# throughhole.net
KiCad netlist of a schematic drawn in EAGLE
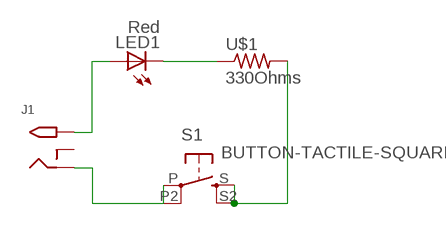
[diagram p0: schematic, sheet 1]

(export (version "E")
  (design (tool "Eeschema 10.0.6"))
  (components
    (comp (ref "J1")
      (value "2.1MMJACKTHM")
      (footprint "eagle-import:PJ-102A")
      (libsource (lib "eagle-import") (part "2.1MMJACKTHM"))
    )
    (comp (ref "LED1")
      (value "Red")
      (footprint "eagle-import:LED5MM")
      (libsource (lib "eagle-import") (part "LED5MM"))
    )
    (comp (ref "S1")
      (value "BUTTON-TACTILE-SQUARE")
      (footprint "eagle-import:BUTTON-TACTILE-SQUARE-ADAFRUIT1010")
      (libsource (lib "eagle-import") (part "BUTTON-TACTILE-SQUARE"))
    )
    (comp (ref "U$1")
      (value "330Ohms")
      (footprint "eagle-import:RESAD1160W55L680D260_HS")
      (libsource (lib "eagle-import") (part "RESISTORTH-1/4W-CARBON"))
    )
  )
  (nets
    (net (code "1") (name "Net-(J1-PadTIP)") (class "Default")
      (node (ref "J1") (pin "TIP") (pinfunction "TIP_TIP") (pintype "bidirectional"))
      (node (ref "LED1") (pin "A") (pinfunction "A_A") (pintype "passive"))
    )
    (net (code "2") (name "Net-(LED1-C)") (class "Default")
      (node (ref "LED1") (pin "K") (pinfunction "C_K") (pintype "passive"))
      (node (ref "U$1") (pin "1") (pinfunction "1_1") (pintype "passive"))
    )
    (net (code "3") (name "Net-(S1-P1)") (class "Default")
      (node (ref "J1") (pin "RING") (pinfunction "RING_RING") (pintype "bidirectional"))
      (node (ref "S1") (pin "P") (pinfunction "P_P") (pintype "passive"))
      (node (ref "S1") (pin "P2") (pinfunction "P1_P2") (pintype "passive"))
    )
    (net (code "4") (name "Net-(S1-S1)") (class "Default")
      (node (ref "S1") (pin "S") (pinfunction "S_S") (pintype "passive"))
      (node (ref "S1") (pin "S2") (pinfunction "S1_S2") (pintype "passive"))
      (node (ref "U$1") (pin "2") (pinfunction "2_2") (pintype "passive"))
    )
    (net (code "5") (name "unconnected-(J1-PadRING_SW)") (class "Default")
      (node (ref "J1") (pin "RING_SW") (pinfunction "RING_SW_RING_SW") (pintype "bidirectional"))
    )
  )
)
